# TopLevel.net
KiCad netlist of a schematic drawn in Altium Designer
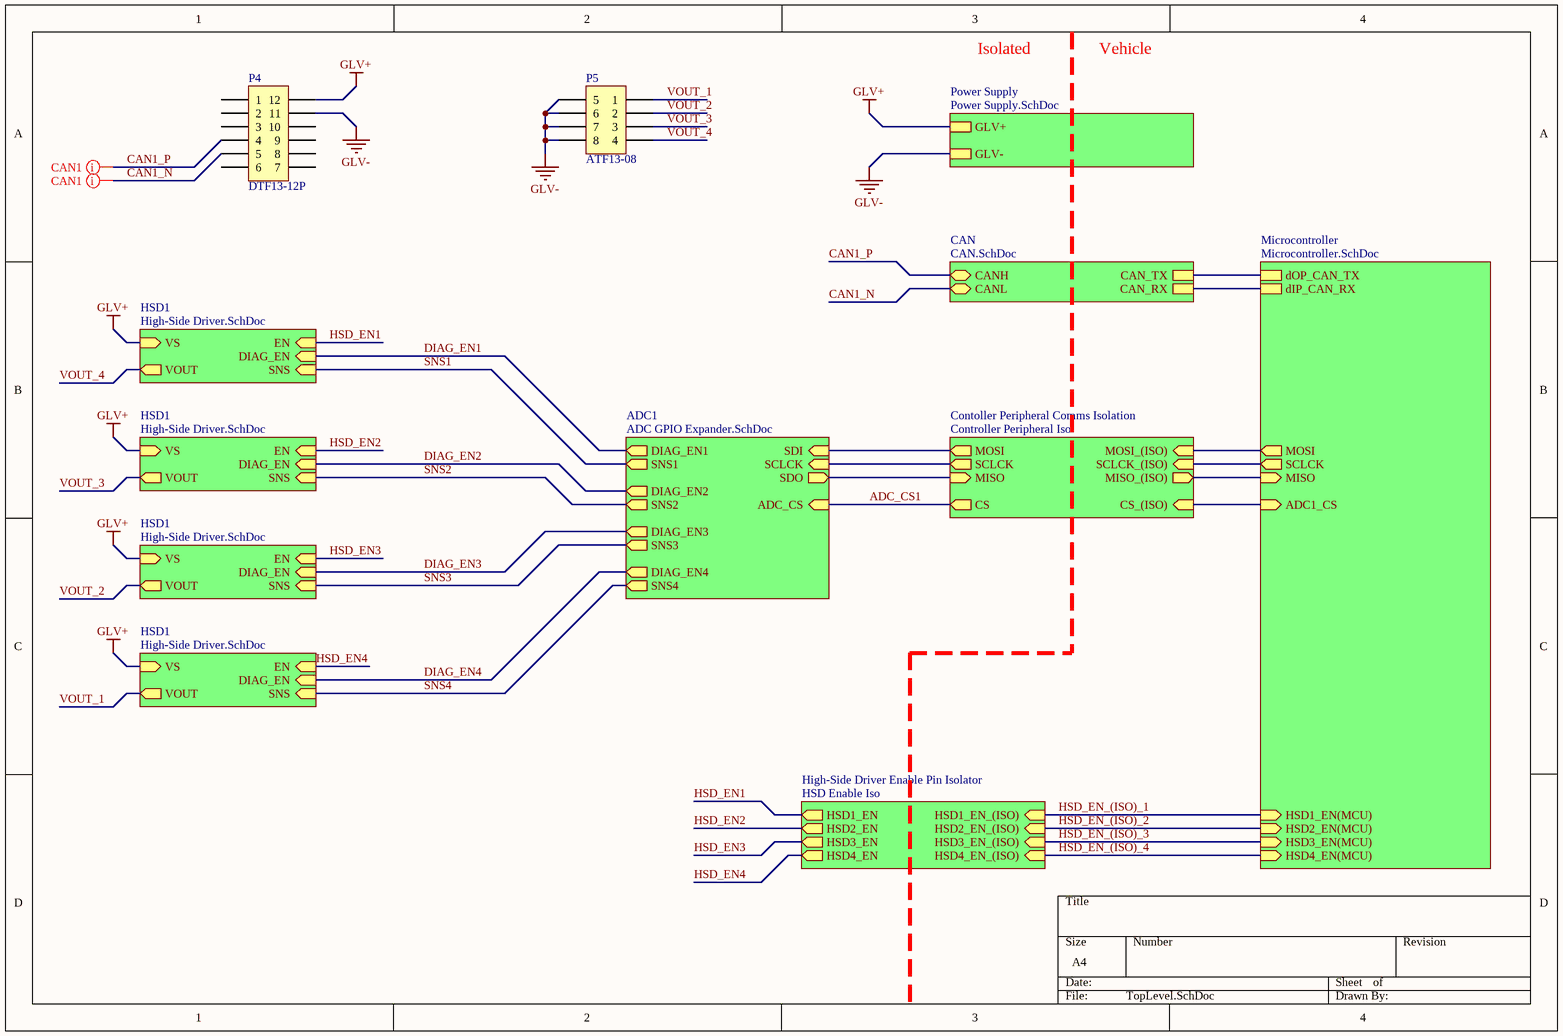
[diagram p0: TopLevel.SchDoc]

(export (version "E")
  (design (tool "Eeschema 10.0.6"))
  (components
    (comp (ref "P4")
      (value "DTF13-12P")
      (footprint "DTF13-12P")
      (fields (field (name "DIGIKEY PART NUMBER") "1734-1861-ND") (field (name "CONTACT") "Copper Alloy"))
      (libsource (lib "ts_standard_connectors") (part "DT13-12P"))
    )
    (comp (ref "P5")
      (value "ATF13-08")
      (footprint "ATF13-08")
      (libsource (lib "ts_standard_connectors") (part "ATF13-08"))
    )
  )
  (nets
    (net (code "3") (name "/CAN1_N") (class "Default")
      (node (ref "P4") (pin "5") (pinfunction "5_5") (pintype "power_in"))
    )
    (net (code "4") (name "/CAN1_P") (class "Default")
      (node (ref "P4") (pin "4") (pinfunction "4_4") (pintype "power_in"))
    )
    (net (code "29") (name "/VOUT_1") (class "Default")
      (node (ref "P5") (pin "1") (pinfunction "1_1") (pintype "power_in"))
    )
    (net (code "30") (name "/VOUT_2") (class "Default")
      (node (ref "P5") (pin "2") (pinfunction "2_2") (pintype "power_in"))
    )
    (net (code "31") (name "/VOUT_3") (class "Default")
      (node (ref "P5") (pin "3") (pinfunction "3_3") (pintype "power_in"))
    )
    (net (code "32") (name "/VOUT_4") (class "Default")
      (node (ref "P5") (pin "4") (pinfunction "4_4") (pintype "power_in"))
    )
    (net (code "33") (name "GLV+") (class "Default")
      (node (ref "P4") (pin "12") (pinfunction "12_12") (pintype "passive"))
    )
    (net (code "34") (name "GLV-") (class "Default")
      (node (ref "P4") (pin "11") (pinfunction "11_11") (pintype "passive"))
      (node (ref "P5") (pin "5") (pinfunction "5_5") (pintype "power_in"))
      (node (ref "P5") (pin "6") (pinfunction "6_6") (pintype "power_in"))
      (node (ref "P5") (pin "7") (pinfunction "7_7") (pintype "passive"))
      (node (ref "P5") (pin "8") (pinfunction "8_8") (pintype "passive"))
    )
    (net (code "35") (name "unconnected-(P4-Pad1)") (class "Default")
      (node (ref "P4") (pin "1") (pinfunction "1_1") (pintype "power_in"))
    )
    (net (code "36") (name "unconnected-(P4-Pad2)") (class "Default")
      (node (ref "P4") (pin "2") (pinfunction "2_2") (pintype "power_in"))
    )
    (net (code "37") (name "unconnected-(P4-Pad3)") (class "Default")
      (node (ref "P4") (pin "3") (pinfunction "3_3") (pintype "power_in"))
    )
    (net (code "38") (name "unconnected-(P4-Pad6)") (class "Default")
      (node (ref "P4") (pin "6") (pinfunction "6_6") (pintype "power_in"))
    )
    (net (code "39") (name "unconnected-(P4-Pad7)") (class "Default")
      (node (ref "P4") (pin "7") (pinfunction "7_7") (pintype "passive"))
    )
    (net (code "40") (name "unconnected-(P4-Pad8)") (class "Default")
      (node (ref "P4") (pin "8") (pinfunction "8_8") (pintype "passive"))
    )
    (net (code "41") (name "unconnected-(P4-Pad9)") (class "Default")
      (node (ref "P4") (pin "9") (pinfunction "9_9") (pintype "passive"))
    )
    (net (code "42") (name "unconnected-(P4-Pad10)") (class "Default")
      (node (ref "P4") (pin "10") (pinfunction "10_10") (pintype "passive"))
    )
  )
)
